# Extension_connector.net
KiCad netlist of a schematic drawn in Altium Designer
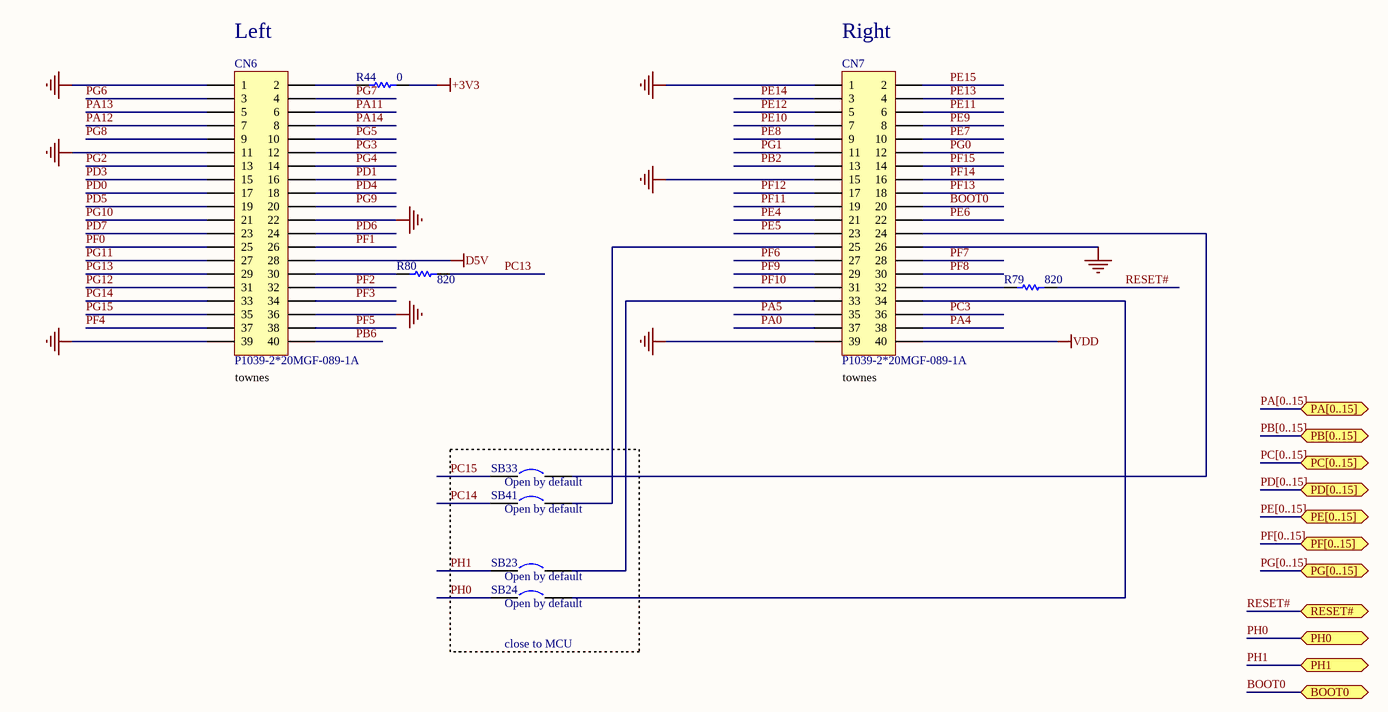
[diagram p0: Extension connector.SCHDOC]

(export (version "E")
  (design (tool "Eeschema 10.0.6"))
  (components
    (comp (ref "CN6")
      (value "P1039-2*20MGF-089-1A")
      (footprint "FTR-120-53-L-D-LC")
      (description "Header, 20-Pin, Dual row")
      (fields (field (name "PUBLISHER") "Altium Limited"))
      (libsource (lib "mb1045") (part "FTR-120-53-L-D-LC"))
    )
    (comp (ref "CN7")
      (value "P1039-2*20MGF-089-1A")
      (footprint "FTR-120-53-L-D-LC")
      (description "Header, 20-Pin, Dual row")
      (fields (field (name "PUBLISHER") "Altium Limited"))
      (libsource (lib "mb1045") (part "FTR-120-53-L-D-LC"))
    )
    (comp (ref "R44")
      (value "0")
      (footprint "0603R")
      (description "Resistor")
      (fields (field (name "PUBLISHER") "Altium Limited"))
      (libsource (lib "Miscellaneous Devices") (part "Res1"))
    )
    (comp (ref "R79")
      (value "820")
      (footprint "0402R")
      (description "Resistor")
      (fields (field (name "PUBLISHER") "Altium Limited"))
      (libsource (lib "Miscellaneous Devices") (part "Res1"))
    )
    (comp (ref "R80")
      (value "820")
      (footprint "0402R")
      (description "Resistor")
      (fields (field (name "PUBLISHER") "Altium Limited"))
      (libsource (lib "Miscellaneous Devices") (part "Res1"))
    )
    (comp (ref "SB23")
      (value "Open by default")
      (footprint "SB_0603")
      (description "Circuit Breaker")
      (fields (field (name "PUBLISHER") "Altium Limited"))
      (libsource (lib "Miscellaneous Devices") (part "Circuit Breaker"))
    )
    (comp (ref "SB24")
      (value "Open by default")
      (footprint "SB_0603")
      (description "Circuit Breaker")
      (fields (field (name "PUBLISHER") "Altium Limited"))
      (libsource (lib "Miscellaneous Devices") (part "Circuit Breaker"))
    )
    (comp (ref "SB33")
      (value "Open by default")
      (footprint "SB_0603")
      (description "Circuit Breaker")
      (fields (field (name "PUBLISHER") "Altium Limited"))
      (libsource (lib "Miscellaneous Devices") (part "Circuit Breaker"))
    )
    (comp (ref "SB41")
      (value "Open by default")
      (footprint "SB_0603")
      (description "Circuit Breaker")
      (fields (field (name "PUBLISHER") "Altium Limited"))
      (libsource (lib "Miscellaneous Devices") (part "Circuit Breaker"))
    )
  )
  (nets
    (net (code "49") (name "+3V3") (class "Default")
      (node (ref "R44") (pin "1") (pinfunction "1_1") (pintype "passive"))
    )
    (net (code "50") (name "/BOOT0") (class "Default")
      (node (ref "CN7") (pin "20") (pinfunction "20_20") (pintype "passive"))
    )
    (net (code "51") (name "/PA0") (class "Default")
      (node (ref "CN7") (pin "37") (pinfunction "37_37") (pintype "passive"))
    )
    (net (code "52") (name "/PA4") (class "Default")
      (node (ref "CN7") (pin "38") (pinfunction "38_38") (pintype "passive"))
    )
    (net (code "53") (name "/PA5") (class "Default")
      (node (ref "CN7") (pin "35") (pinfunction "35_35") (pintype "passive"))
    )
    (net (code "54") (name "/PA11") (class "Default")
      (node (ref "CN6") (pin "6") (pinfunction "6_6") (pintype "passive"))
    )
    (net (code "55") (name "/PA12") (class "Default")
      (node (ref "CN6") (pin "7") (pinfunction "7_7") (pintype "passive"))
    )
    (net (code "56") (name "/PA13") (class "Default")
      (node (ref "CN6") (pin "5") (pinfunction "5_5") (pintype "passive"))
    )
    (net (code "57") (name "/PA14") (class "Default")
      (node (ref "CN6") (pin "8") (pinfunction "8_8") (pintype "passive"))
    )
    (net (code "59") (name "/PB2") (class "Default")
      (node (ref "CN7") (pin "13") (pinfunction "13_13") (pintype "passive"))
    )
    (net (code "60") (name "/PB6") (class "Default")
      (node (ref "CN6") (pin "40") (pinfunction "40_40") (pintype "passive"))
    )
    (net (code "62") (name "/PC3") (class "Default")
      (node (ref "CN7") (pin "36") (pinfunction "36_36") (pintype "passive"))
    )
    (net (code "63") (name "/PC13") (class "Default")
      (node (ref "R80") (pin "2") (pinfunction "2_2") (pintype "passive"))
    )
    (net (code "64") (name "/PC14") (class "Default")
      (node (ref "SB41") (pin "1") (pinfunction "1_1") (pintype "passive"))
    )
    (net (code "65") (name "/PC15") (class "Default")
      (node (ref "SB33") (pin "1") (pinfunction "1_1") (pintype "passive"))
    )
    (net (code "67") (name "/PD0") (class "Default")
      (node (ref "CN6") (pin "17") (pinfunction "17_17") (pintype "passive"))
    )
    (net (code "68") (name "/PD1") (class "Default")
      (node (ref "CN6") (pin "16") (pinfunction "16_16") (pintype "passive"))
    )
    (net (code "69") (name "/PD3") (class "Default")
      (node (ref "CN6") (pin "15") (pinfunction "15_15") (pintype "passive"))
    )
    (net (code "70") (name "/PD4") (class "Default")
      (node (ref "CN6") (pin "18") (pinfunction "18_18") (pintype "passive"))
    )
    (net (code "71") (name "/PD5") (class "Default")
      (node (ref "CN6") (pin "19") (pinfunction "19_19") (pintype "passive"))
    )
    (net (code "72") (name "/PD6") (class "Default")
      (node (ref "CN6") (pin "24") (pinfunction "24_24") (pintype "passive"))
    )
    (net (code "73") (name "/PD7") (class "Default")
      (node (ref "CN6") (pin "23") (pinfunction "23_23") (pintype "passive"))
    )
    (net (code "75") (name "/PE4") (class "Default")
      (node (ref "CN7") (pin "21") (pinfunction "21_21") (pintype "passive"))
    )
    (net (code "76") (name "/PE5") (class "Default")
      (node (ref "CN7") (pin "23") (pinfunction "23_23") (pintype "passive"))
    )
    (net (code "77") (name "/PE6") (class "Default")
      (node (ref "CN7") (pin "22") (pinfunction "22_22") (pintype "passive"))
    )
    (net (code "78") (name "/PE7") (class "Default")
      (node (ref "CN7") (pin "10") (pinfunction "10_10") (pintype "passive"))
    )
    (net (code "79") (name "/PE8") (class "Default")
      (node (ref "CN7") (pin "9") (pinfunction "9_9") (pintype "passive"))
    )
    (net (code "80") (name "/PE9") (class "Default")
      (node (ref "CN7") (pin "8") (pinfunction "8_8") (pintype "passive"))
    )
    (net (code "81") (name "/PE10") (class "Default")
      (node (ref "CN7") (pin "7") (pinfunction "7_7") (pintype "passive"))
    )
    (net (code "82") (name "/PE11") (class "Default")
      (node (ref "CN7") (pin "6") (pinfunction "6_6") (pintype "passive"))
    )
    (net (code "83") (name "/PE12") (class "Default")
      (node (ref "CN7") (pin "5") (pinfunction "5_5") (pintype "passive"))
    )
    (net (code "84") (name "/PE13") (class "Default")
      (node (ref "CN7") (pin "4") (pinfunction "4_4") (pintype "passive"))
    )
    (net (code "85") (name "/PE14") (class "Default")
      (node (ref "CN7") (pin "3") (pinfunction "3_3") (pintype "passive"))
    )
    (net (code "86") (name "/PE15") (class "Default")
      (node (ref "CN7") (pin "2") (pinfunction "2_2") (pintype "passive"))
    )
    (net (code "88") (name "/PF0") (class "Default")
      (node (ref "CN6") (pin "25") (pinfunction "25_25") (pintype "passive"))
    )
    (net (code "89") (name "/PF1") (class "Default")
      (node (ref "CN6") (pin "26") (pinfunction "26_26") (pintype "passive"))
    )
    (net (code "90") (name "/PF2") (class "Default")
      (node (ref "CN6") (pin "32") (pinfunction "32_32") (pintype "passive"))
    )
    (net (code "91") (name "/PF3") (class "Default")
      (node (ref "CN6") (pin "34") (pinfunction "34_34") (pintype "passive"))
    )
    (net (code "92") (name "/PF4") (class "Default")
      (node (ref "CN6") (pin "37") (pinfunction "37_37") (pintype "passive"))
    )
    (net (code "93") (name "/PF5") (class "Default")
      (node (ref "CN6") (pin "38") (pinfunction "38_38") (pintype "passive"))
    )
    (net (code "94") (name "/PF6") (class "Default")
      (node (ref "CN7") (pin "27") (pinfunction "27_27") (pintype "passive"))
    )
    (net (code "95") (name "/PF7") (class "Default")
      (node (ref "CN7") (pin "28") (pinfunction "28_28") (pintype "passive"))
    )
    (net (code "96") (name "/PF8") (class "Default")
      (node (ref "CN7") (pin "30") (pinfunction "30_30") (pintype "passive"))
    )
    (net (code "97") (name "/PF9") (class "Default")
      (node (ref "CN7") (pin "29") (pinfunction "29_29") (pintype "passive"))
    )
    (net (code "98") (name "/PF10") (class "Default")
      (node (ref "CN7") (pin "31") (pinfunction "31_31") (pintype "passive"))
    )
    (net (code "99") (name "/PF11") (class "Default")
      (node (ref "CN7") (pin "19") (pinfunction "19_19") (pintype "passive"))
    )
    (net (code "100") (name "/PF12") (class "Default")
      (node (ref "CN7") (pin "17") (pinfunction "17_17") (pintype "passive"))
    )
    (net (code "101") (name "/PF13") (class "Default")
      (node (ref "CN7") (pin "18") (pinfunction "18_18") (pintype "passive"))
    )
    (net (code "102") (name "/PF14") (class "Default")
      (node (ref "CN7") (pin "16") (pinfunction "16_16") (pintype "passive"))
    )
    (net (code "103") (name "/PF15") (class "Default")
      (node (ref "CN7") (pin "14") (pinfunction "14_14") (pintype "passive"))
    )
    (net (code "105") (name "/PG0") (class "Default")
      (node (ref "CN7") (pin "12") (pinfunction "12_12") (pintype "passive"))
    )
    (net (code "106") (name "/PG1") (class "Default")
      (node (ref "CN7") (pin "11") (pinfunction "11_11") (pintype "passive"))
    )
    (net (code "107") (name "/PG2") (class "Default")
      (node (ref "CN6") (pin "13") (pinfunction "13_13") (pintype "passive"))
    )
    (net (code "108") (name "/PG3") (class "Default")
      (node (ref "CN6") (pin "12") (pinfunction "12_12") (pintype "passive"))
    )
    (net (code "109") (name "/PG4") (class "Default")
      (node (ref "CN6") (pin "14") (pinfunction "14_14") (pintype "passive"))
    )
    (net (code "110") (name "/PG5") (class "Default")
      (node (ref "CN6") (pin "10") (pinfunction "10_10") (pintype "passive"))
    )
    (net (code "111") (name "/PG6") (class "Default")
      (node (ref "CN6") (pin "3") (pinfunction "3_3") (pintype "passive"))
    )
    (net (code "112") (name "/PG7") (class "Default")
      (node (ref "CN6") (pin "4") (pinfunction "4_4") (pintype "passive"))
    )
    (net (code "113") (name "/PG8") (class "Default")
      (node (ref "CN6") (pin "9") (pinfunction "9_9") (pintype "passive"))
    )
    (net (code "114") (name "/PG9") (class "Default")
      (node (ref "CN6") (pin "20") (pinfunction "20_20") (pintype "passive"))
    )
    (net (code "115") (name "/PG10") (class "Default")
      (node (ref "CN6") (pin "21") (pinfunction "21_21") (pintype "passive"))
    )
    (net (code "116") (name "/PG11") (class "Default")
      (node (ref "CN6") (pin "27") (pinfunction "27_27") (pintype "passive"))
    )
    (net (code "117") (name "/PG12") (class "Default")
      (node (ref "CN6") (pin "31") (pinfunction "31_31") (pintype "passive"))
    )
    (net (code "118") (name "/PG13") (class "Default")
      (node (ref "CN6") (pin "29") (pinfunction "29_29") (pintype "passive"))
    )
    (net (code "119") (name "/PG14") (class "Default")
      (node (ref "CN6") (pin "33") (pinfunction "33_33") (pintype "passive"))
    )
    (net (code "120") (name "/PG15") (class "Default")
      (node (ref "CN6") (pin "35") (pinfunction "35_35") (pintype "passive"))
    )
    (net (code "122") (name "/PH0") (class "Default")
      (node (ref "SB24") (pin "1") (pinfunction "1_1") (pintype "passive"))
    )
    (net (code "123") (name "/PH1") (class "Default")
      (node (ref "SB23") (pin "1") (pinfunction "1_1") (pintype "passive"))
    )
    (net (code "124") (name "/RESET#") (class "Default")
      (node (ref "R79") (pin "1") (pinfunction "1_1") (pintype "passive"))
    )
    (net (code "125") (name "D5V") (class "Default")
      (node (ref "CN6") (pin "28") (pinfunction "28_28") (pintype "passive"))
    )
    (net (code "126") (name "GND") (class "Default")
      (node (ref "CN6") (pin "1") (pinfunction "1_1") (pintype "passive"))
      (node (ref "CN6") (pin "11") (pinfunction "11_11") (pintype "passive"))
      (node (ref "CN6") (pin "22") (pinfunction "22_22") (pintype "passive"))
      (node (ref "CN6") (pin "36") (pinfunction "36_36") (pintype "passive"))
      (node (ref "CN6") (pin "39") (pinfunction "39_39") (pintype "passive"))
      (node (ref "CN7") (pin "1") (pinfunction "1_1") (pintype "passive"))
      (node (ref "CN7") (pin "15") (pinfunction "15_15") (pintype "passive"))
      (node (ref "CN7") (pin "26") (pinfunction "26_26") (pintype "passive"))
      (node (ref "CN7") (pin "39") (pinfunction "39_39") (pintype "passive"))
    )
    (net (code "127") (name "Net-(CN6-Pad2)") (class "Default")
      (node (ref "CN6") (pin "2") (pinfunction "2_2") (pintype "passive"))
      (node (ref "R44") (pin "2") (pinfunction "2_2") (pintype "passive"))
    )
    (net (code "128") (name "Net-(CN6-Pad30)") (class "Default")
      (node (ref "CN6") (pin "30") (pinfunction "30_30") (pintype "passive"))
      (node (ref "R80") (pin "1") (pinfunction "1_1") (pintype "passive"))
    )
    (net (code "129") (name "Net-(CN7-Pad24)") (class "Default")
      (node (ref "CN7") (pin "24") (pinfunction "24_24") (pintype "passive"))
      (node (ref "SB33") (pin "2") (pinfunction "2_2") (pintype "passive"))
    )
    (net (code "130") (name "Net-(CN7-Pad25)") (class "Default")
      (node (ref "CN7") (pin "25") (pinfunction "25_25") (pintype "passive"))
      (node (ref "SB41") (pin "2") (pinfunction "2_2") (pintype "passive"))
    )
    (net (code "131") (name "Net-(CN7-Pad32)") (class "Default")
      (node (ref "CN7") (pin "32") (pinfunction "32_32") (pintype "passive"))
      (node (ref "R79") (pin "2") (pinfunction "2_2") (pintype "passive"))
    )
    (net (code "132") (name "Net-(CN7-Pad33)") (class "Default")
      (node (ref "CN7") (pin "33") (pinfunction "33_33") (pintype "passive"))
      (node (ref "SB23") (pin "2") (pinfunction "2_2") (pintype "passive"))
    )
    (net (code "133") (name "Net-(CN7-Pad34)") (class "Default")
      (node (ref "CN7") (pin "34") (pinfunction "34_34") (pintype "passive"))
      (node (ref "SB24") (pin "2") (pinfunction "2_2") (pintype "passive"))
    )
    (net (code "134") (name "VDD") (class "Default")
      (node (ref "CN7") (pin "40") (pinfunction "40_40") (pintype "passive"))
    )
  )
)
